# 220V_Control.net
KiCad netlist of a schematic drawn in Altium Designer
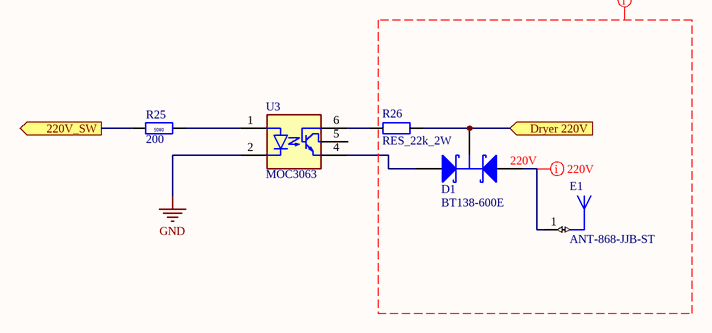
[diagram p0: 220V_Control.SchDoc]

(export (version "E")
  (design (tool "Eeschema 10.0.6"))
  (components
    (comp (ref "D1")
      (value "BT138-600E")
      (footprint "TO-220")
      (description "Schottky Rectifier 20 A TO-220")
      (fields (field (name "PUBLISHER") "Altium Limited"))
      (libsource (lib "Discrete") (part "MBR20xx"))
    )
    (comp (ref "E1")
      (value "ANT-868-JJB-ST")
      (footprint "ANT-XXX-JJB-ST")
      (description "Embeddable 1/4-wave Monopole Antenna, JJB Series, 868MHz, 7mm Dia. Package, Straight")
      (libsource (lib "Connectors") (part "ANT-868-JJB-ST"))
    )
    (comp (ref "R25")
      (value "200")
      (footprint "RESC2012-0805M")
      (description "Resistor 0805")
      (fields (field (name "Comment") "RESC_0805_R"))
      (libsource (lib "Passive") (part "RESC_0805_R"))
    )
    (comp (ref "R26")
      (value "RES_22k_2W")
      (footprint "PCBComponent_1")
      (description "Резистор 2 Вт")
      (libsource (lib "Res_2W") (part "RES_22k_2W"))
    )
    (comp (ref "U3")
      (value "MOC3063")
      (footprint "DIP6-400")
      (description "CNY17 phototransistor optoclupler")
      (libsource (lib "Discrete") (part "CNY17"))
    )
  )
  (nets
    (net (code "1") (name "/220V_SW") (class "Default")
      (node (ref "R25") (pin "2") (pinfunction "2_2") (pintype "passive"))
    )
    (net (code "2") (name "/Dryer 220V") (class "Default")
      (node (ref "D1") (pin "2") (pinfunction "K_2") (pintype "passive"))
      (node (ref "R26") (pin "2") (pintype "passive"))
    )
    (net (code "3") (name "GND") (class "Default")
      (node (ref "U3") (pin "2") (pinfunction "2_2") (pintype "passive"))
    )
    (net (code "4") (name "Net-(D1-A1)") (class "Default")
      (node (ref "D1") (pin "1") (pinfunction "A1_1") (pintype "passive"))
      (node (ref "E1") (pin "1") (pinfunction "FEED_1") (pintype "bidirectional"))
    )
    (net (code "5") (name "Net-(D1-A2)") (class "Default")
      (node (ref "D1") (pin "3") (pinfunction "A2_3") (pintype "passive"))
      (node (ref "U3") (pin "4") (pinfunction "4_4") (pintype "passive"))
    )
    (net (code "6") (name "Net-(R25-Pad1)") (class "Default")
      (node (ref "R25") (pin "1") (pinfunction "1_1") (pintype "passive"))
      (node (ref "U3") (pin "1") (pinfunction "1_1") (pintype "passive"))
    )
    (net (code "7") (name "Net-(R26-Pad1)") (class "Default")
      (node (ref "R26") (pin "1") (pintype "passive"))
      (node (ref "U3") (pin "6") (pinfunction "6_6") (pintype "passive"))
    )
    (net (code "8") (name "unconnected-(U3-Pad3)") (class "Default")
      (node (ref "U3") (pin "3") (pinfunction "3_3") (pintype "passive"))
    )
    (net (code "9") (name "unconnected-(U3-Pad5)") (class "Default")
      (node (ref "U3") (pin "5") (pinfunction "5_5") (pintype "passive"))
    )
  )
)
